# esp_relay_hongngoai.net
KiCad netlist of a schematic drawn in Altium Designer
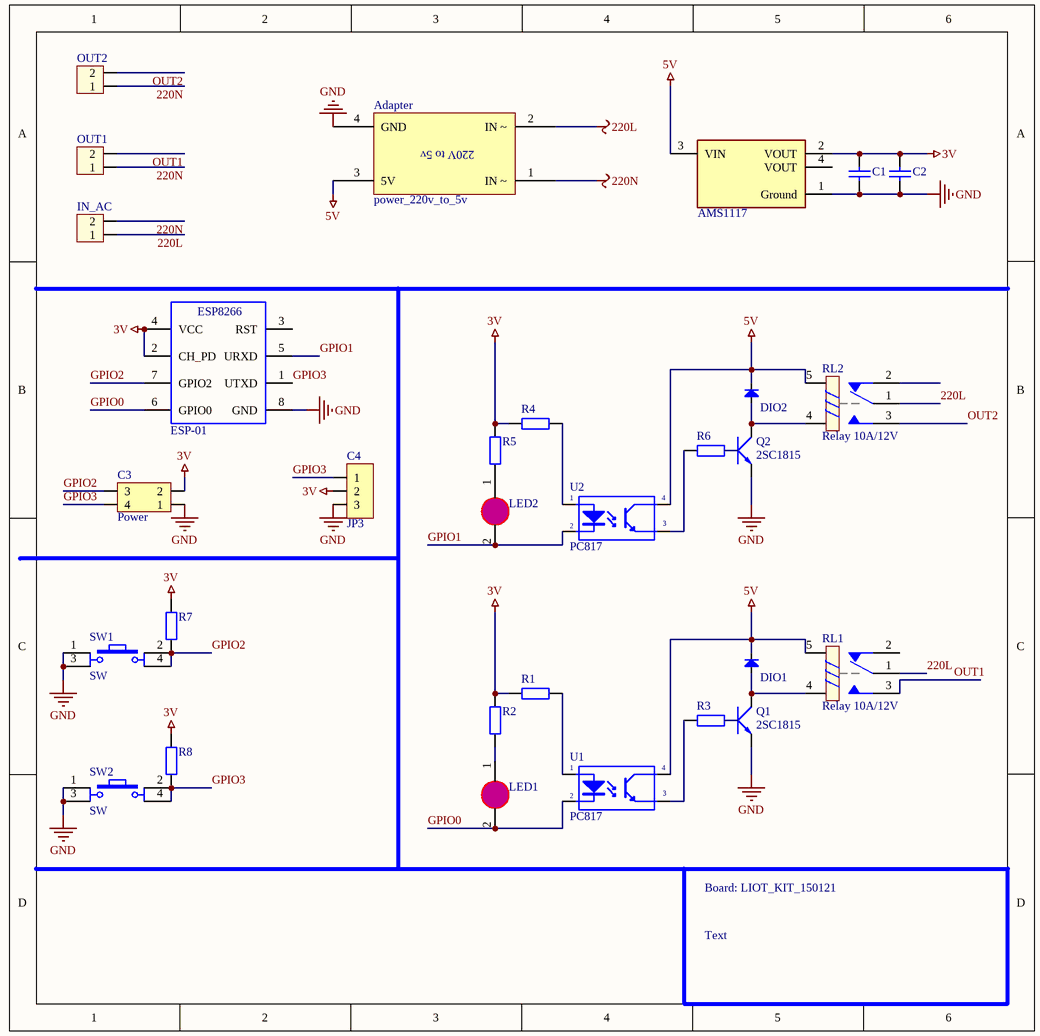
[diagram p0: esp_relay_hongngoai.SchDoc]

(export (version "E")
  (design (tool "Eeschema 10.0.6"))
  (components
    (comp (ref "Adapter")
      (value "power_220v_to_5v")
      (footprint "power_220V_to_5V")
      (libsource (lib "My Library") (part "power_220v_to_5v"))
    )
    (comp (ref "AMS1117")
      (value "AMS1117-3.3")
      (footprint "Advanced_Monolithic_Systems_AMS1117_IPC_A")
      (libsource (lib "IC_Advanced_Monolithic_Systems_AMS1117-3.3_eec") (part "AMS1117-3.3"))
    )
    (comp (ref "C1")
      (value "Capacitor Ceramic")
      (footprint "C0805")
      (description "Capacitor")
      (fields (field (name "PUBLISHER") "Altium Limited"))
      (libsource (lib "My Library") (part "CapSMD"))
    )
    (comp (ref "C2")
      (value "Capacitor Ceramic")
      (footprint "C0805")
      (description "Capacitor")
      (fields (field (name "PUBLISHER") "Altium Limited"))
      (libsource (lib "My Library") (part "CapSMD"))
    )
    (comp (ref "C3")
      (value "Power")
      (footprint "JP2-D2T")
      (description "WR-PHD 2.54 mm Dual Socket Header")
      (fields
        (field (name "MANUFACTURER") "Würth Elektronik eiSos GmbH")
        (field (name "PARTNO") "61300421821")
        (field (name "CREATED BY") "Karrer Zheng")
      )
      (libsource (lib "TechMT.VN_Lib_Project v2") (part "JP2x2"))
    )
    (comp (ref "C4")
      (value "JP3")
      (footprint "JP3-D1T")
      (description "WR-PHD 2.54 mm Angled Socket Header")
      (fields
        (field (name "MANUFACTURER") "Würth Elektronik eiSos GmbH")
        (field (name "PARTNO") "613003143121")
        (field (name "CREATED BY") "Karrer Zheng")
      )
      (libsource (lib "TechMT.VN_Lib_Project v2") (part "JP3"))
    )
    (comp (ref "DIO1")
      (value "Diode SMD")
      (footprint "DIO-SMD-106")
      (description "Default Diode")
      (fields (field (name "PUBLISHER") "Altium Limited"))
      (libsource (lib "My Library") (part "Diode SMD"))
    )
    (comp (ref "DIO2")
      (value "Diode SMD")
      (footprint "DIO-SMD-106")
      (description "Default Diode")
      (fields (field (name "PUBLISHER") "Altium Limited"))
      (libsource (lib "My Library") (part "Diode SMD"))
    )
    (comp (ref "IN_AC")
      (value "~")
      (footprint "HED2")
      (description "Header 2 (Green)")
      (libsource (lib "My Library") (part "Hed2"))
    )
    (comp (ref "LED1")
      (value "~")
      (footprint "LED0805")
      (description "LED SMD 0805")
      (libsource (lib "My Library") (part "LED0805"))
    )
    (comp (ref "LED2")
      (value "~")
      (footprint "LED0805")
      (description "LED SMD 0805")
      (libsource (lib "My Library") (part "LED0805"))
    )
    (comp (ref "OUT1")
      (value "~")
      (footprint "HED2")
      (description "Header 2 (Green)")
      (libsource (lib "My Library") (part "Hed2"))
    )
    (comp (ref "OUT2")
      (value "~")
      (footprint "HED2")
      (description "Header 2 (Green)")
      (libsource (lib "My Library") (part "Hed2"))
    )
    (comp (ref "Q1")
      (value "2SC1815")
      (footprint "TO92-123")
      (description "NPN 600mW, ECB")
      (libsource (lib "TechMT.VN_Lib_Project v2") (part "2SC1815"))
    )
    (comp (ref "Q2")
      (value "2SC1815")
      (footprint "TO92-123")
      (description "NPN 600mW, ECB")
      (libsource (lib "TechMT.VN_Lib_Project v2") (part "2SC1815"))
    )
    (comp (ref "R1")
      (value "~")
      (footprint "SM-0805")
      (description "Resistor SMD")
      (libsource (lib "My Library") (part "RM"))
    )
    (comp (ref "R2")
      (value "~")
      (footprint "SM-0805")
      (description "Resistor SMD")
      (libsource (lib "My Library") (part "RM"))
    )
    (comp (ref "R3")
      (value "~")
      (footprint "SM-0805")
      (description "Resistor SMD")
      (libsource (lib "My Library") (part "RM"))
    )
    (comp (ref "R4")
      (value "~")
      (footprint "SM-0805")
      (description "Resistor SMD")
      (libsource (lib "My Library") (part "RM"))
    )
    (comp (ref "R5")
      (value "~")
      (footprint "SM-0805")
      (description "Resistor SMD")
      (libsource (lib "My Library") (part "RM"))
    )
    (comp (ref "R6")
      (value "~")
      (footprint "SM-0805")
      (description "Resistor SMD")
      (libsource (lib "My Library") (part "RM"))
    )
    (comp (ref "R7")
      (value "~")
      (footprint "SM-0805")
      (description "Resistor SMD")
      (libsource (lib "My Library") (part "RM"))
    )
    (comp (ref "R8")
      (value "~")
      (footprint "SM-0805")
      (description "Resistor SMD")
      (libsource (lib "My Library") (part "RM"))
    )
    (comp (ref "RL1")
      (value "Relay 10A/12V")
      (footprint "RL_SPDT_10A")
      (description "Relay SPDT,10A - 12VDC 5 Pin")
      (libsource (lib "My Library") (part "Relay 1"))
    )
    (comp (ref "RL2")
      (value "Relay 10A/12V")
      (footprint "RL_SPDT_10A")
      (description "Relay SPDT,10A - 12VDC 5 Pin")
      (libsource (lib "My Library") (part "Relay 1"))
    )
    (comp (ref "SW1")
      (value "SW")
      (footprint "SW4")
      (description "Switch button 4 pin")
      (libsource (lib "My Library") (part "SW4"))
    )
    (comp (ref "SW2")
      (value "SW")
      (footprint "SW4")
      (description "Switch button 4 pin")
      (libsource (lib "My Library") (part "SW4"))
    )
    (comp (ref "U1")
      (value "PC817")
      (footprint "DIP4")
      (description "Single Opto")
      (libsource (lib "TechMT.VN_Lib_Project v2") (part "PC817"))
    )
    (comp (ref "U2")
      (value "PC817")
      (footprint "DIP4")
      (description "Single Opto")
      (libsource (lib "TechMT.VN_Lib_Project v2") (part "PC817"))
    )
    (comp (ref "U3")
      (value "ESP-01")
      (footprint "ESP8266")
      (description "ESP-12 Wi-Fi Module")
      (libsource (lib "My Library") (part "ESP8266-01"))
    )
  )
  (nets
    (net (code "2") (name "/GPIO0") (class "Default")
      (node (ref "LED1") (pin "2") (pinfunction "K_2") (pintype "passive"))
      (node (ref "U1") (pin "2") (pinfunction "K_2") (pintype "passive"))
      (node (ref "U3") (pin "6") (pinfunction "GPIO0_6") (pintype "passive"))
    )
    (net (code "3") (name "/GPIO1") (class "Default")
      (node (ref "LED2") (pin "2") (pinfunction "K_2") (pintype "passive"))
      (node (ref "U2") (pin "2") (pinfunction "K_2") (pintype "passive"))
      (node (ref "U3") (pin "5") (pinfunction "URXD_5") (pintype "passive"))
    )
    (net (code "4") (name "/GPIO2") (class "Default")
      (node (ref "C3") (pin "3") (pinfunction "3_3") (pintype "passive"))
      (node (ref "R7") (pin "1") (pinfunction "1_1") (pintype "passive"))
      (node (ref "SW1") (pin "2") (pintype "passive"))
      (node (ref "SW1") (pin "4") (pintype "passive"))
      (node (ref "U3") (pin "7") (pinfunction "GPIO2_7") (pintype "passive"))
    )
    (net (code "5") (name "/GPIO3") (class "Default")
      (node (ref "C3") (pin "4") (pinfunction "4_4") (pintype "passive"))
      (node (ref "C4") (pin "1") (pinfunction "1_1") (pintype "passive"))
      (node (ref "R8") (pin "1") (pinfunction "1_1") (pintype "passive"))
      (node (ref "SW2") (pin "2") (pintype "passive"))
      (node (ref "SW2") (pin "4") (pintype "passive"))
      (node (ref "U3") (pin "1") (pinfunction "UTXD_1") (pintype "passive"))
    )
    (net (code "6") (name "/OUT1") (class "Default")
      (node (ref "OUT1") (pin "2") (pinfunction "2_2") (pintype "passive"))
      (node (ref "RL1") (pin "3") (pinfunction "3_3") (pintype "passive"))
    )
    (net (code "7") (name "/OUT2") (class "Default")
      (node (ref "OUT2") (pin "2") (pinfunction "2_2") (pintype "passive"))
      (node (ref "RL2") (pin "3") (pinfunction "3_3") (pintype "passive"))
    )
    (net (code "8") (name "3V") (class "Default")
      (node (ref "AMS1117") (pin "2") (pinfunction "VOUT_2") (pintype "passive"))
      (node (ref "C1") (pin "2") (pinfunction "2_2") (pintype "passive"))
      (node (ref "C2") (pin "2") (pinfunction "2_2") (pintype "passive"))
      (node (ref "C3") (pin "2") (pinfunction "2_2") (pintype "passive"))
      (node (ref "C4") (pin "2") (pinfunction "2_2") (pintype "passive"))
      (node (ref "R1") (pin "1") (pinfunction "1_1") (pintype "passive"))
      (node (ref "R2") (pin "2") (pinfunction "2_2") (pintype "passive"))
      (node (ref "R4") (pin "1") (pinfunction "1_1") (pintype "passive"))
      (node (ref "R5") (pin "2") (pinfunction "2_2") (pintype "passive"))
      (node (ref "R7") (pin "2") (pinfunction "2_2") (pintype "passive"))
      (node (ref "R8") (pin "2") (pinfunction "2_2") (pintype "passive"))
      (node (ref "U3") (pin "2") (pinfunction "CH_PD_2") (pintype "passive"))
      (node (ref "U3") (pin "4") (pinfunction "VCC_4") (pintype "passive"))
    )
    (net (code "9") (name "5V") (class "Default")
      (node (ref "AMS1117") (pin "3") (pinfunction "VIN_3") (pintype "power_in"))
      (node (ref "Adapter") (pin "3") (pinfunction "5V_3") (pintype "passive"))
      (node (ref "DIO1") (pin "2") (pinfunction "K_2") (pintype "passive"))
      (node (ref "DIO2") (pin "2") (pinfunction "K_2") (pintype "passive"))
      (node (ref "RL1") (pin "5") (pinfunction "5_5") (pintype "passive"))
      (node (ref "RL2") (pin "5") (pinfunction "5_5") (pintype "passive"))
      (node (ref "U1") (pin "4") (pinfunction "C_4") (pintype "passive"))
      (node (ref "U2") (pin "4") (pinfunction "C_4") (pintype "passive"))
    )
    (net (code "10") (name "220L") (class "Default")
      (node (ref "Adapter") (pin "2") (pinfunction "IN_~_2") (pintype "passive"))
      (node (ref "IN_AC") (pin "1") (pinfunction "1_1") (pintype "passive"))
      (node (ref "RL1") (pin "1") (pinfunction "1_1") (pintype "passive"))
      (node (ref "RL2") (pin "1") (pinfunction "1_1") (pintype "passive"))
    )
    (net (code "11") (name "220N") (class "Default")
      (node (ref "Adapter") (pin "1") (pinfunction "IN_~_1") (pintype "passive"))
      (node (ref "IN_AC") (pin "2") (pinfunction "2_2") (pintype "passive"))
      (node (ref "OUT1") (pin "1") (pinfunction "1_1") (pintype "passive"))
      (node (ref "OUT2") (pin "1") (pinfunction "1_1") (pintype "passive"))
    )
    (net (code "12") (name "GND") (class "Default")
      (node (ref "AMS1117") (pin "1") (pinfunction "Ground_1") (pintype "power_in"))
      (node (ref "Adapter") (pin "4") (pinfunction "GND_4") (pintype "passive"))
      (node (ref "C1") (pin "1") (pinfunction "1_1") (pintype "passive"))
      (node (ref "C2") (pin "1") (pinfunction "1_1") (pintype "passive"))
      (node (ref "C3") (pin "1") (pinfunction "1_1") (pintype "passive"))
      (node (ref "C4") (pin "3") (pinfunction "3_3") (pintype "passive"))
      (node (ref "Q1") (pin "1") (pinfunction "E_1") (pintype "passive"))
      (node (ref "Q2") (pin "1") (pinfunction "E_1") (pintype "passive"))
      (node (ref "SW1") (pin "1") (pintype "passive"))
      (node (ref "SW1") (pin "3") (pintype "passive"))
      (node (ref "SW2") (pin "1") (pintype "passive"))
      (node (ref "SW2") (pin "3") (pintype "passive"))
      (node (ref "U3") (pin "8") (pinfunction "GND_8") (pintype "passive"))
    )
    (net (code "13") (name "Net-(DIO1-A)") (class "Default")
      (node (ref "DIO1") (pin "1") (pinfunction "A_1") (pintype "passive"))
      (node (ref "Q1") (pin "2") (pinfunction "C_2") (pintype "passive"))
      (node (ref "RL1") (pin "4") (pinfunction "4_4") (pintype "passive"))
    )
    (net (code "14") (name "Net-(DIO2-A)") (class "Default")
      (node (ref "DIO2") (pin "1") (pinfunction "A_1") (pintype "passive"))
      (node (ref "Q2") (pin "2") (pinfunction "C_2") (pintype "passive"))
      (node (ref "RL2") (pin "4") (pinfunction "4_4") (pintype "passive"))
    )
    (net (code "15") (name "Net-(LED1-A)") (class "Default")
      (node (ref "LED1") (pin "1") (pinfunction "A_1") (pintype "passive"))
      (node (ref "R2") (pin "1") (pinfunction "1_1") (pintype "passive"))
    )
    (net (code "16") (name "Net-(LED2-A)") (class "Default")
      (node (ref "LED2") (pin "1") (pinfunction "A_1") (pintype "passive"))
      (node (ref "R5") (pin "1") (pinfunction "1_1") (pintype "passive"))
    )
    (net (code "17") (name "Net-(Q1-B)") (class "Default")
      (node (ref "Q1") (pin "3") (pinfunction "B_3") (pintype "passive"))
      (node (ref "R3") (pin "2") (pinfunction "2_2") (pintype "passive"))
    )
    (net (code "18") (name "Net-(Q2-B)") (class "Default")
      (node (ref "Q2") (pin "3") (pinfunction "B_3") (pintype "passive"))
      (node (ref "R6") (pin "2") (pinfunction "2_2") (pintype "passive"))
    )
    (net (code "19") (name "Net-(U1-A)") (class "Default")
      (node (ref "R1") (pin "2") (pinfunction "2_2") (pintype "passive"))
      (node (ref "U1") (pin "1") (pinfunction "A_1") (pintype "passive"))
    )
    (net (code "20") (name "Net-(U1-E)") (class "Default")
      (node (ref "R3") (pin "1") (pinfunction "1_1") (pintype "passive"))
      (node (ref "U1") (pin "3") (pinfunction "E_3") (pintype "passive"))
    )
    (net (code "21") (name "Net-(U2-A)") (class "Default")
      (node (ref "R4") (pin "2") (pinfunction "2_2") (pintype "passive"))
      (node (ref "U2") (pin "1") (pinfunction "A_1") (pintype "passive"))
    )
    (net (code "22") (name "Net-(U2-E)") (class "Default")
      (node (ref "R6") (pin "1") (pinfunction "1_1") (pintype "passive"))
      (node (ref "U2") (pin "3") (pinfunction "E_3") (pintype "passive"))
    )
    (net (code "23") (name "unconnected-(AMS1117-VOUT-Pad4)") (class "Default")
      (node (ref "AMS1117") (pin "4") (pinfunction "VOUT_4") (pintype "passive"))
    )
    (net (code "24") (name "unconnected-(RL1-Pad2)") (class "Default")
      (node (ref "RL1") (pin "2") (pinfunction "2_2") (pintype "passive"))
    )
    (net (code "25") (name "unconnected-(RL2-Pad2)") (class "Default")
      (node (ref "RL2") (pin "2") (pinfunction "2_2") (pintype "passive"))
    )
    (net (code "26") (name "unconnected-(U3-RST-Pad3)") (class "Default")
      (node (ref "U3") (pin "3") (pinfunction "RST_3") (pintype "passive"))
    )
  )
)
